# Sheet1.net
KiCad netlist of a schematic drawn in Altium Designer
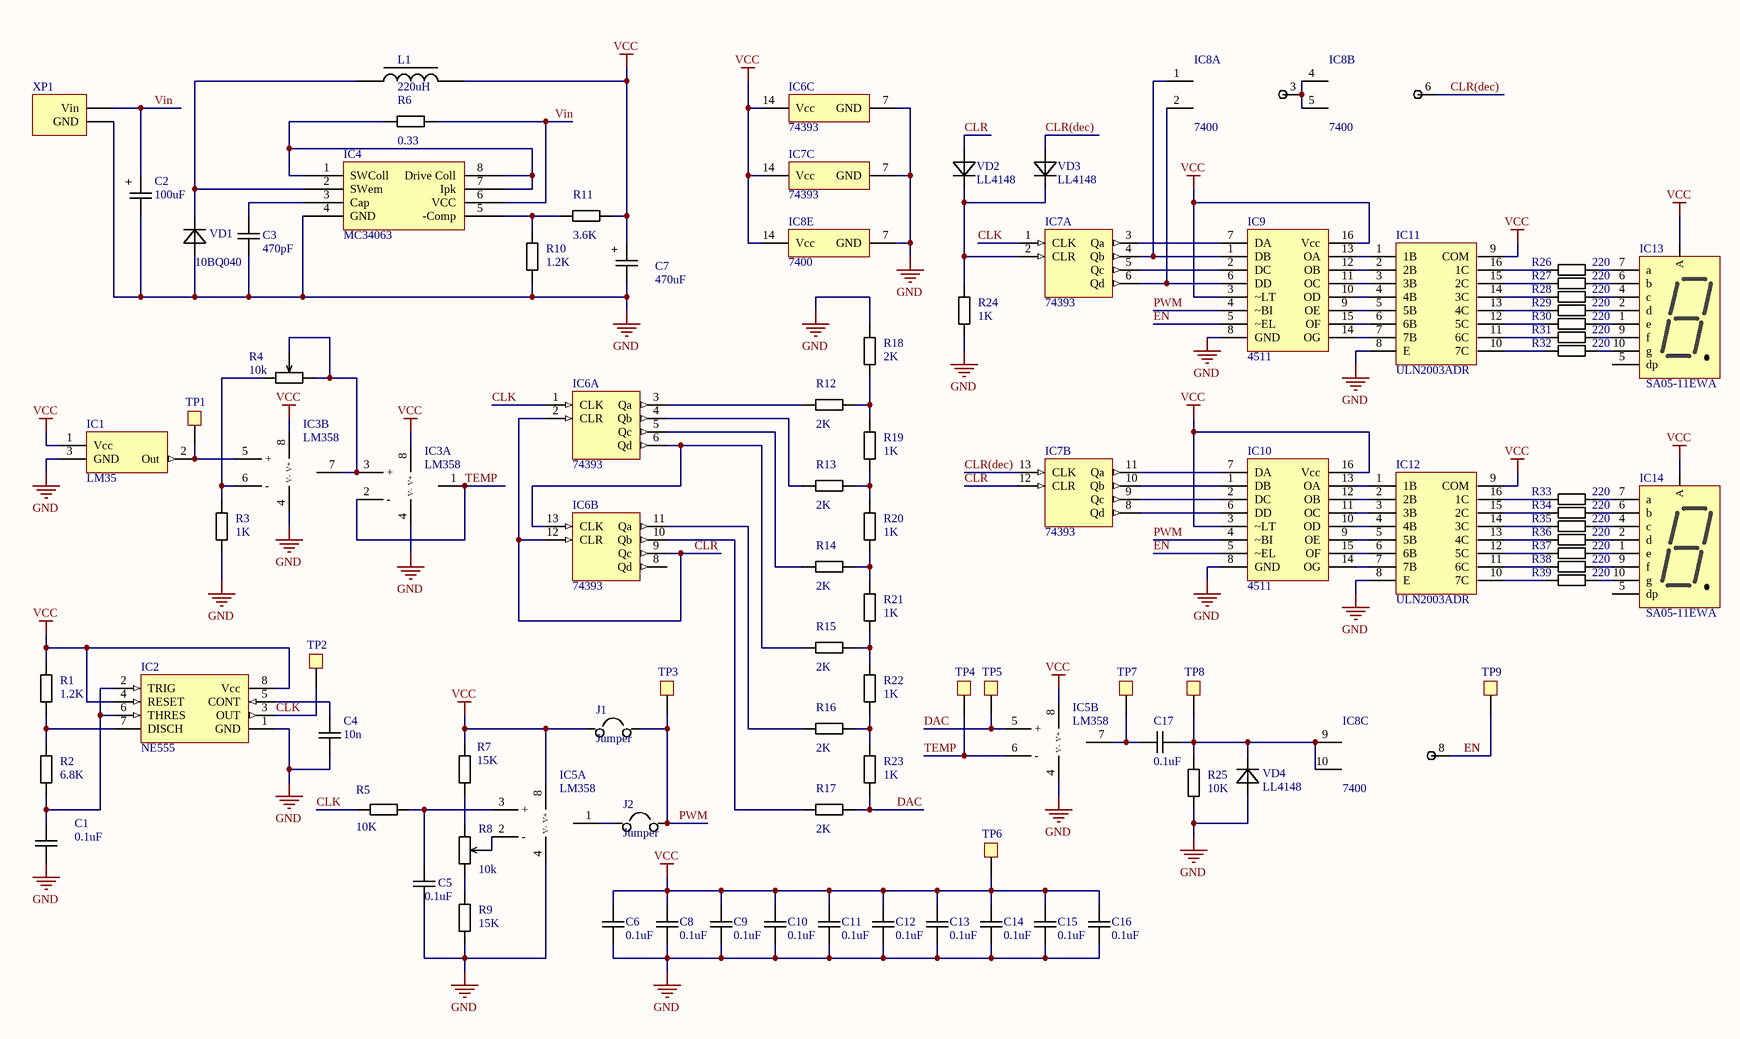
[diagram p0: Sheet1.SchDoc]

(export (version "E")
  (design (tool "Eeschema 10.0.6"))
  (components
    (comp (ref "C1") (value "0.1uF") (footprint "CAP0805") (libsource (lib "Schlib") (part "Cap0805")))
    (comp (ref "C2") (value "100uF") (footprint "CAP-SMD-E") (libsource (lib "Schlib") (part "Cap+")))
    (comp (ref "C3") (value "470pF") (footprint "CAP0805") (libsource (lib "Schlib") (part "Cap0805")))
    (comp (ref "C4") (value "10n") (footprint "CAP0805") (libsource (lib "Schlib") (part "Cap0805")))
    (comp (ref "C5") (value "0.1uF") (footprint "CAP0805") (libsource (lib "Schlib") (part "Cap0805")))
    (comp (ref "C6") (value "0.1uF") (footprint "CAP0805") (libsource (lib "Schlib") (part "Cap0805")))
    (comp (ref "C7") (value "470uF") (footprint "CAP-SMD-E") (libsource (lib "Schlib") (part "Cap+")))
    (comp (ref "C8") (value "0.1uF") (footprint "CAP0805") (libsource (lib "Schlib") (part "Cap0805")))
    (comp (ref "C9") (value "0.1uF") (footprint "CAP0805") (libsource (lib "Schlib") (part "Cap0805")))
    (comp (ref "C10") (value "0.1uF") (footprint "CAP0805") (libsource (lib "Schlib") (part "Cap0805")))
    (comp (ref "C11") (value "0.1uF") (footprint "CAP0805") (libsource (lib "Schlib") (part "Cap0805")))
    (comp (ref "C12") (value "0.1uF") (footprint "CAP0805") (libsource (lib "Schlib") (part "Cap0805")))
    (comp (ref "C13") (value "0.1uF") (footprint "CAP0805") (libsource (lib "Schlib") (part "Cap0805")))
    (comp (ref "C14") (value "0.1uF") (footprint "CAP0805") (libsource (lib "Schlib") (part "Cap0805")))
    (comp (ref "C15") (value "0.1uF") (footprint "CAP0805") (libsource (lib "Schlib") (part "Cap0805")))
    (comp (ref "C16") (value "0.1uF") (footprint "CAP0805") (libsource (lib "Schlib") (part "Cap0805")))
    (comp (ref "C17") (value "0.1uF") (footprint "CAP0805") (libsource (lib "Schlib") (part "Cap0805")))
    (comp (ref "IC1") (value "LM35") (footprint "TO92") (libsource (lib "Schlib") (part "LM35")))
    (comp (ref "IC2") (value "NE555") (footprint "SOIC8") (libsource (lib "Schlib") (part "NE555")))
    (comp (ref "IC3") (value "LM358") (footprint "SOIC8") (libsource (lib "Schlib") (part "LM358")))
    (comp (ref "IC4") (value "MC34063") (footprint "SOIC8") (libsource (lib "Schlib") (part "MC34063")))
    (comp (ref "IC5") (value "LM358") (footprint "SOIC8") (libsource (lib "Schlib") (part "LM358")))
    (comp (ref "IC6") (value "74393") (footprint "SOIC-14(3.9mm)") (libsource (lib "Schlib") (part "74393")))
    (comp (ref "IC7") (value "74393") (footprint "SOIC-14(3.9mm)") (libsource (lib "Schlib") (part "74393")))
    (comp (ref "IC8") (value "7400") (footprint "SOIC-14(3.9mm)") (libsource (lib "Schlib") (part "7400")))
    (comp (ref "IC9") (value "4511") (footprint "DIP16") (libsource (lib "Schlib") (part "4511")))
    (comp (ref "IC10") (value "4511") (footprint "DIP16") (libsource (lib "Schlib") (part "4511")))
    (comp (ref "IC11")
      (value "ULN2003ADR")
      (footprint "SOIC16")
      (libsource (lib "Schlib") (part "ULN2003ADR"))
    )
    (comp (ref "IC12")
      (value "ULN2003ADR")
      (footprint "SOIC16")
      (libsource (lib "Schlib") (part "ULN2003ADR"))
    )
    (comp (ref "IC13")
      (value "SA05-11EWA")
      (footprint "SA05-11EWA")
      (libsource (lib "Schlib") (part "SA05-11EWA"))
    )
    (comp (ref "IC14")
      (value "SA05-11EWA")
      (footprint "SA05-11EWA")
      (libsource (lib "Schlib") (part "SA05-11EWA"))
    )
    (comp (ref "J1") (value "Jumper") (footprint "RES0805") (libsource (lib "Schlib") (part "Jumper0805")))
    (comp (ref "J2") (value "Jumper") (footprint "RES0805") (libsource (lib "Schlib") (part "Jumper0805")))
    (comp (ref "L1") (value "220uH") (footprint "LQH55") (libsource (lib "Schlib") (part "Coil")))
    (comp (ref "R1") (value "1.2K") (footprint "RES0805") (libsource (lib "") (part "Res0805_1")))
    (comp (ref "R2") (value "6.8K") (footprint "RES0805") (libsource (lib "") (part "Res0805_1")))
    (comp (ref "R3") (value "1K") (footprint "RES0805") (libsource (lib "") (part "Res0805_1")))
    (comp (ref "R4") (value "10k") (footprint "POT") (libsource (lib "") (part "POT_1")))
    (comp (ref "R5") (value "10K") (footprint "RES0805") (libsource (lib "") (part "Res0805_2")))
    (comp (ref "R6") (value "0.33") (footprint "RES0805") (libsource (lib "Schlib") (part "Res0805")))
    (comp (ref "R7") (value "15K") (footprint "RES0805") (libsource (lib "") (part "Res0805_3")))
    (comp (ref "R8") (value "10k") (footprint "POT") (libsource (lib "Schlib") (part "POT")))
    (comp (ref "R9") (value "15K") (footprint "RES0805") (libsource (lib "") (part "Res0805_3")))
    (comp (ref "R10") (value "1.2K") (footprint "RES0805") (libsource (lib "") (part "Res0805_1")))
    (comp (ref "R11") (value "3.6K") (footprint "RES0805") (libsource (lib "") (part "Res0805_2")))
    (comp (ref "R12") (value "2K") (footprint "RES0805") (libsource (lib "Schlib") (part "Res0805")))
    (comp (ref "R13") (value "2K") (footprint "RES0805") (libsource (lib "Schlib") (part "Res0805")))
    (comp (ref "R14") (value "2K") (footprint "RES0805") (libsource (lib "Schlib") (part "Res0805")))
    (comp (ref "R15") (value "2K") (footprint "RES0805") (libsource (lib "Schlib") (part "Res0805")))
    (comp (ref "R16") (value "2K") (footprint "RES0805") (libsource (lib "Schlib") (part "Res0805")))
    (comp (ref "R17") (value "2K") (footprint "RES0805") (libsource (lib "Schlib") (part "Res0805")))
    (comp (ref "R18") (value "2K") (footprint "RES0805") (libsource (lib "") (part "Res0805_1")))
    (comp (ref "R19") (value "1K") (footprint "RES0805") (libsource (lib "") (part "Res0805_1")))
    (comp (ref "R20") (value "1K") (footprint "RES0805") (libsource (lib "") (part "Res0805_1")))
    (comp (ref "R21") (value "1K") (footprint "RES0805") (libsource (lib "") (part "Res0805_1")))
    (comp (ref "R22") (value "1K") (footprint "RES0805") (libsource (lib "") (part "Res0805_1")))
    (comp (ref "R23") (value "1K") (footprint "RES0805") (libsource (lib "") (part "Res0805_1")))
    (comp (ref "R24") (value "1K") (footprint "RES0805") (libsource (lib "") (part "Res0805_1")))
    (comp (ref "R25") (value "10K") (footprint "RES0805") (libsource (lib "") (part "Res0805_1")))
    (comp (ref "R26") (value "220") (footprint "RES0805") (libsource (lib "Schlib") (part "Res0805")))
    (comp (ref "R27") (value "220") (footprint "RES0805") (libsource (lib "Schlib") (part "Res0805")))
    (comp (ref "R28") (value "220") (footprint "RES0805") (libsource (lib "Schlib") (part "Res0805")))
    (comp (ref "R29") (value "220") (footprint "RES0805") (libsource (lib "Schlib") (part "Res0805")))
    (comp (ref "R30") (value "220") (footprint "RES0805") (libsource (lib "Schlib") (part "Res0805")))
    (comp (ref "R31") (value "220") (footprint "RES0805") (libsource (lib "Schlib") (part "Res0805")))
    (comp (ref "R32") (value "220") (footprint "RES0805") (libsource (lib "Schlib") (part "Res0805")))
    (comp (ref "R33") (value "220") (footprint "RES0805") (libsource (lib "Schlib") (part "Res0805")))
    (comp (ref "R34") (value "220") (footprint "RES0805") (libsource (lib "Schlib") (part "Res0805")))
    (comp (ref "R35") (value "220") (footprint "RES0805") (libsource (lib "Schlib") (part "Res0805")))
    (comp (ref "R36") (value "220") (footprint "RES0805") (libsource (lib "Schlib") (part "Res0805")))
    (comp (ref "R37") (value "220") (footprint "RES0805") (libsource (lib "Schlib") (part "Res0805")))
    (comp (ref "R38") (value "220") (footprint "RES0805") (libsource (lib "Schlib") (part "Res0805")))
    (comp (ref "R39") (value "220") (footprint "RES0805") (libsource (lib "Schlib") (part "Res0805")))
    (comp (ref "TP1") (value "TestPoint") (footprint "TP") (libsource (lib "Schlib") (part "TestPoint")))
    (comp (ref "TP2") (value "TestPoint") (footprint "TP") (libsource (lib "Schlib") (part "TestPoint")))
    (comp (ref "TP3") (value "TestPoint") (footprint "TP") (libsource (lib "Schlib") (part "TestPoint")))
    (comp (ref "TP4") (value "TestPoint") (footprint "TP") (libsource (lib "Schlib") (part "TestPoint")))
    (comp (ref "TP5") (value "TestPoint") (footprint "TP") (libsource (lib "Schlib") (part "TestPoint")))
    (comp (ref "TP6") (value "TestPoint") (footprint "TP") (libsource (lib "Schlib") (part "TestPoint")))
    (comp (ref "TP7") (value "TestPoint") (footprint "TP") (libsource (lib "Schlib") (part "TestPoint")))
    (comp (ref "TP8") (value "TestPoint") (footprint "TP") (libsource (lib "Schlib") (part "TestPoint")))
    (comp (ref "TP9") (value "TestPoint") (footprint "TP") (libsource (lib "Schlib") (part "TestPoint")))
    (comp (ref "VD1")
      (value "10BQ040")
      (footprint "DIODESMB")
      (libsource (lib "Schlib") (part "10BQ040(diode)"))
    )
    (comp (ref "VD2")
      (value "LL4148")
      (footprint "DIOMELF")
      (libsource (lib "Schlib") (part "LL4148(diode)"))
    )
    (comp (ref "VD3")
      (value "LL4148")
      (footprint "DIOMELF")
      (libsource (lib "Schlib") (part "LL4148(diode)"))
    )
    (comp (ref "VD4")
      (value "LL4148")
      (footprint "DIOMELF")
      (libsource (lib "Schlib") (part "LL4148(diode)"))
    )
    (comp (ref "XP1") (value "XP") (footprint "XP") (libsource (lib "Schlib") (part "XP")))
  )
  (nets
    (net (code "1") (name "/CLK") (class "Default")
      (node (ref "IC2") (pin "3") (pinfunction "OUT_3") (pintype "output"))
      (node (ref "IC6") (pin "1") (pinfunction "CLK_1") (pintype "input"))
      (node (ref "IC7") (pin "1") (pinfunction "CLK_1") (pintype "input"))
      (node (ref "R5") (pin "2") (pinfunction "2_2") (pintype "passive"))
      (node (ref "TP2") (pin "0") (pinfunction "0_0") (pintype "passive"))
    )
    (net (code "2") (name "/CLR") (class "Default")
      (node (ref "IC6") (pin "12") (pinfunction "CLR_12") (pintype "input"))
      (node (ref "IC6") (pin "2") (pinfunction "CLR_2") (pintype "input"))
      (node (ref "IC6") (pin "9") (pinfunction "Qc_9") (pintype "output"))
      (node (ref "IC7") (pin "12") (pinfunction "CLR_12") (pintype "input"))
      (node (ref "VD2") (pin "A") (pinfunction "A_A") (pintype "passive"))
    )
    (net (code "3") (name "/CLR(dec)") (class "Default")
      (node (ref "IC7") (pin "13") (pinfunction "CLK_13") (pintype "input"))
      (node (ref "IC8") (pin "6") (pinfunction "2Y_6") (pintype "passive"))
      (node (ref "VD3") (pin "A") (pinfunction "A_A") (pintype "passive"))
    )
    (net (code "4") (name "/DAC") (class "Default")
      (node (ref "IC5") (pin "5") (pinfunction "+_5") (pintype "passive"))
      (node (ref "R17") (pin "2") (pinfunction "2_2") (pintype "passive"))
      (node (ref "R23") (pin "1") (pinfunction "1_1") (pintype "passive"))
      (node (ref "TP5") (pin "0") (pinfunction "0_0") (pintype "passive"))
    )
    (net (code "5") (name "/EN") (class "Default")
      (node (ref "IC10") (pin "5") (pinfunction "~EL_5") (pintype "passive"))
      (node (ref "IC8") (pin "8") (pinfunction "3Y_8") (pintype "passive"))
      (node (ref "IC9") (pin "5") (pinfunction "~EL_5") (pintype "passive"))
      (node (ref "TP9") (pin "0") (pinfunction "0_0") (pintype "passive"))
    )
    (net (code "6") (name "/PWM") (class "Default")
      (node (ref "IC10") (pin "4") (pinfunction "~BI_4") (pintype "passive"))
      (node (ref "IC9") (pin "4") (pinfunction "~BI_4") (pintype "passive"))
      (node (ref "J1") (pin "2") (pinfunction "2_2") (pintype "passive"))
      (node (ref "J2") (pin "2") (pinfunction "2_2") (pintype "passive"))
      (node (ref "TP3") (pin "0") (pinfunction "0_0") (pintype "passive"))
    )
    (net (code "7") (name "/TEMP") (class "Default")
      (node (ref "IC3") (pin "1") (pinfunction "Q1_1") (pintype "passive"))
      (node (ref "IC3") (pin "2") (pinfunction "-_2") (pintype "passive"))
      (node (ref "IC5") (pin "6") (pinfunction "-_6") (pintype "passive"))
      (node (ref "TP4") (pin "0") (pinfunction "0_0") (pintype "passive"))
    )
    (net (code "8") (name "/Vin") (class "Default")
      (node (ref "C2") (pin "A") (pinfunction "2_A") (pintype "passive"))
      (node (ref "IC4") (pin "6") (pinfunction "VCC_6") (pintype "power_in"))
      (node (ref "R6") (pin "2") (pinfunction "2_2") (pintype "passive"))
      (node (ref "XP1") (pin "V") (pinfunction "Vin_V") (pintype "power_in"))
    )
    (net (code "9") (name "GND") (class "Default")
      (node (ref "C1") (pin "2") (pinfunction "2_2") (pintype "passive"))
      (node (ref "C10") (pin "1") (pinfunction "1_1") (pintype "passive"))
      (node (ref "C11") (pin "1") (pinfunction "1_1") (pintype "passive"))
      (node (ref "C12") (pin "1") (pinfunction "1_1") (pintype "passive"))
      (node (ref "C13") (pin "1") (pinfunction "1_1") (pintype "passive"))
      (node (ref "C14") (pin "1") (pinfunction "1_1") (pintype "passive"))
      (node (ref "C15") (pin "1") (pinfunction "1_1") (pintype "passive"))
      (node (ref "C16") (pin "1") (pinfunction "1_1") (pintype "passive"))
      (node (ref "C2") (pin "C") (pinfunction "1_C") (pintype "passive"))
      (node (ref "C3") (pin "2") (pinfunction "2_2") (pintype "passive"))
      (node (ref "C4") (pin "1") (pinfunction "1_1") (pintype "passive"))
      (node (ref "C5") (pin "1") (pinfunction "1_1") (pintype "passive"))
      (node (ref "C6") (pin "1") (pinfunction "1_1") (pintype "passive"))
      (node (ref "C7") (pin "C") (pinfunction "1_C") (pintype "passive"))
      (node (ref "C8") (pin "1") (pinfunction "1_1") (pintype "passive"))
      (node (ref "C9") (pin "1") (pinfunction "1_1") (pintype "passive"))
      (node (ref "IC1") (pin "3") (pinfunction "GND_3") (pintype "power_in"))
      (node (ref "IC10") (pin "8") (pinfunction "GND_8") (pintype "passive"))
      (node (ref "IC11") (pin "8") (pinfunction "E_8") (pintype "passive"))
      (node (ref "IC12") (pin "8") (pinfunction "E_8") (pintype "passive"))
      (node (ref "IC2") (pin "1") (pinfunction "GND_1") (pintype "power_in"))
      (node (ref "IC3") (pin "4") (pinfunction "V-_4") (pintype "power_in"))
      (node (ref "IC4") (pin "4") (pinfunction "GND_4") (pintype "power_in"))
      (node (ref "IC5") (pin "4") (pinfunction "V-_4") (pintype "power_in"))
      (node (ref "IC6") (pin "7") (pinfunction "GND_7") (pintype "power_in"))
      (node (ref "IC7") (pin "7") (pinfunction "GND_7") (pintype "power_in"))
      (node (ref "IC8") (pin "7") (pinfunction "GND_7") (pintype "power_in"))
      (node (ref "IC9") (pin "8") (pinfunction "GND_8") (pintype "passive"))
      (node (ref "R10") (pin "1") (pinfunction "1_1") (pintype "passive"))
      (node (ref "R18") (pin "2") (pinfunction "2_2") (pintype "passive"))
      (node (ref "R24") (pin "1") (pinfunction "1_1") (pintype "passive"))
      (node (ref "R25") (pin "1") (pinfunction "1_1") (pintype "passive"))
      (node (ref "R3") (pin "1") (pinfunction "1_1") (pintype "passive"))
      (node (ref "R9") (pin "2") (pinfunction "2_2") (pintype "passive"))
      (node (ref "VD1") (pin "A") (pinfunction "A_A") (pintype "passive"))
      (node (ref "VD4") (pin "A") (pinfunction "A_A") (pintype "passive"))
      (node (ref "XP1") (pin "G") (pinfunction "GND_G") (pintype "power_in"))
    )
    (net (code "10") (name "Net-(IC1-Out)") (class "Default")
      (node (ref "IC1") (pin "2") (pinfunction "Out_2") (pintype "output"))
      (node (ref "IC3") (pin "5") (pinfunction "+_5") (pintype "passive"))
      (node (ref "TP1") (pin "0") (pinfunction "0_0") (pintype "passive"))
    )
    (net (code "11") (name "Net-(IC2-CONT)") (class "Default")
      (node (ref "C4") (pin "2") (pinfunction "2_2") (pintype "passive"))
      (node (ref "IC2") (pin "5") (pinfunction "CONT_5") (pintype "input"))
    )
    (net (code "12") (name "Net-(IC2-DISCH)") (class "Default")
      (node (ref "IC2") (pin "7") (pinfunction "DISCH_7") (pintype "passive"))
      (node (ref "R1") (pin "1") (pinfunction "1_1") (pintype "passive"))
      (node (ref "R2") (pin "2") (pinfunction "2_2") (pintype "passive"))
    )
    (net (code "13") (name "Net-(IC2-THRES)") (class "Default")
      (node (ref "C1") (pin "1") (pinfunction "1_1") (pintype "passive"))
      (node (ref "IC2") (pin "2") (pinfunction "TRIG_2") (pintype "input"))
      (node (ref "IC2") (pin "6") (pinfunction "THRES_6") (pintype "input"))
      (node (ref "R2") (pin "1") (pinfunction "1_1") (pintype "passive"))
    )
    (net (code "14") (name "Net-(IC3A-+)") (class "Default")
      (node (ref "IC3") (pin "3") (pinfunction "+_3") (pintype "passive"))
      (node (ref "IC3") (pin "7") (pinfunction "Q2_7") (pintype "passive"))
      (node (ref "R4") (pin "2") (pinfunction "2_2") (pintype "passive"))
      (node (ref "R4") (pin "3") (pinfunction "3_3") (pintype "passive"))
    )
    (net (code "15") (name "Net-(IC3B--)") (class "Default")
      (node (ref "IC3") (pin "6") (pinfunction "-_6") (pintype "passive"))
      (node (ref "R3") (pin "2") (pinfunction "2_2") (pintype "passive"))
      (node (ref "R4") (pin "1") (pinfunction "1_1") (pintype "passive"))
    )
    (net (code "16") (name "Net-(IC4--Comp)") (class "Default")
      (node (ref "IC4") (pin "5") (pinfunction "-Comp_5") (pintype "passive"))
      (node (ref "R10") (pin "2") (pinfunction "2_2") (pintype "passive"))
      (node (ref "R11") (pin "2") (pinfunction "2_2") (pintype "passive"))
    )
    (net (code "17") (name "Net-(IC4-Cap)") (class "Default")
      (node (ref "C3") (pin "1") (pinfunction "1_1") (pintype "passive"))
      (node (ref "IC4") (pin "3") (pinfunction "Cap_3") (pintype "passive"))
    )
    (net (code "18") (name "Net-(IC4-Drive_Coll)") (class "Default")
      (node (ref "IC4") (pin "1") (pinfunction "SWColl_1") (pintype "passive"))
      (node (ref "IC4") (pin "7") (pinfunction "Ipk_7") (pintype "passive"))
      (node (ref "IC4") (pin "8") (pinfunction "Drive_Coll_8") (pintype "passive"))
      (node (ref "R6") (pin "1") (pinfunction "1_1") (pintype "passive"))
    )
    (net (code "19") (name "Net-(IC4-SWem)") (class "Default")
      (node (ref "IC4") (pin "2") (pinfunction "SWem_2") (pintype "passive"))
      (node (ref "L1") (pin "1") (pinfunction "1_1") (pintype "passive"))
      (node (ref "VD1") (pin "C") (pinfunction "C_C") (pintype "passive"))
    )
    (net (code "20") (name "Net-(IC5A-+)") (class "Default")
      (node (ref "C5") (pin "2") (pinfunction "2_2") (pintype "passive"))
      (node (ref "IC5") (pin "3") (pinfunction "+_3") (pintype "passive"))
      (node (ref "R5") (pin "1") (pinfunction "1_1") (pintype "passive"))
    )
    (net (code "21") (name "Net-(IC5A--)") (class "Default")
      (node (ref "IC5") (pin "2") (pinfunction "-_2") (pintype "passive"))
      (node (ref "R8") (pin "3") (pinfunction "3_3") (pintype "passive"))
    )
    (net (code "22") (name "Net-(IC5A-Q1)") (class "Default")
      (node (ref "IC5") (pin "1") (pinfunction "Q1_1") (pintype "passive"))
      (node (ref "J2") (pin "1") (pinfunction "1_1") (pintype "passive"))
    )
    (net (code "23") (name "Net-(IC5B-Q2)") (class "Default")
      (node (ref "C17") (pin "1") (pinfunction "1_1") (pintype "passive"))
      (node (ref "IC5") (pin "7") (pinfunction "Q2_7") (pintype "passive"))
      (node (ref "TP7") (pin "0") (pinfunction "0_0") (pintype "passive"))
    )
    (net (code "24") (name "Net-(IC6A-Qa)") (class "Default")
      (node (ref "IC6") (pin "3") (pinfunction "Qa_3") (pintype "output"))
      (node (ref "R12") (pin "1") (pinfunction "1_1") (pintype "passive"))
    )
    (net (code "25") (name "Net-(IC6A-Qb)") (class "Default")
      (node (ref "IC6") (pin "4") (pinfunction "Qb_4") (pintype "output"))
      (node (ref "R13") (pin "1") (pinfunction "1_1") (pintype "passive"))
    )
    (net (code "26") (name "Net-(IC6A-Qc)") (class "Default")
      (node (ref "IC6") (pin "5") (pinfunction "Qc_5") (pintype "output"))
      (node (ref "R14") (pin "1") (pinfunction "1_1") (pintype "passive"))
    )
    (net (code "27") (name "Net-(IC6A-Qd)") (class "Default")
      (node (ref "IC6") (pin "13") (pinfunction "CLK_13") (pintype "input"))
      (node (ref "IC6") (pin "6") (pinfunction "Qd_6") (pintype "output"))
      (node (ref "R15") (pin "1") (pinfunction "1_1") (pintype "passive"))
    )
    (net (code "28") (name "Net-(IC6B-Qa)") (class "Default")
      (node (ref "IC6") (pin "11") (pinfunction "Qa_11") (pintype "output"))
      (node (ref "R16") (pin "1") (pinfunction "1_1") (pintype "passive"))
    )
    (net (code "29") (name "Net-(IC6B-Qb)") (class "Default")
      (node (ref "IC6") (pin "10") (pinfunction "Qb_10") (pintype "output"))
      (node (ref "R17") (pin "1") (pinfunction "1_1") (pintype "passive"))
    )
    (net (code "30") (name "Net-(IC7A-CLR)") (class "Default")
      (node (ref "IC7") (pin "2") (pinfunction "CLR_2") (pintype "input"))
      (node (ref "R24") (pin "2") (pinfunction "2_2") (pintype "passive"))
      (node (ref "VD2") (pin "C") (pinfunction "C_C") (pintype "passive"))
      (node (ref "VD3") (pin "C") (pinfunction "C_C") (pintype "passive"))
    )
    (net (code "31") (name "Net-(IC7A-Qa)") (class "Default")
      (node (ref "IC7") (pin "3") (pinfunction "Qa_3") (pintype "output"))
      (node (ref "IC9") (pin "7") (pinfunction "DA_7") (pintype "passive"))
    )
    (net (code "32") (name "Net-(IC7A-Qb)") (class "Default")
      (node (ref "IC7") (pin "4") (pinfunction "Qb_4") (pintype "output"))
      (node (ref "IC8") (pin "1") (pinfunction "1A_1") (pintype "passive"))
      (node (ref "IC9") (pin "1") (pinfunction "DB_1") (pintype "passive"))
    )
    (net (code "33") (name "Net-(IC7A-Qc)") (class "Default")
      (node (ref "IC7") (pin "5") (pinfunction "Qc_5") (pintype "output"))
      (node (ref "IC9") (pin "2") (pinfunction "DC_2") (pintype "passive"))
    )
    (net (code "34") (name "Net-(IC7A-Qd)") (class "Default")
      (node (ref "IC7") (pin "6") (pinfunction "Qd_6") (pintype "output"))
      (node (ref "IC8") (pin "2") (pinfunction "1B_2") (pintype "passive"))
      (node (ref "IC9") (pin "6") (pinfunction "DD_6") (pintype "passive"))
    )
    (net (code "35") (name "Net-(IC8A-1Y)") (class "Default")
      (node (ref "IC8") (pin "3") (pinfunction "1Y_3") (pintype "passive"))
      (node (ref "IC8") (pin "4") (pinfunction "2A_4") (pintype "passive"))
      (node (ref "IC8") (pin "5") (pinfunction "2B_5") (pintype "passive"))
    )
    (net (code "36") (name "Net-(IC8C-3A)") (class "Default")
      (node (ref "C17") (pin "2") (pinfunction "2_2") (pintype "passive"))
      (node (ref "IC8") (pin "10") (pinfunction "3B_10") (pintype "passive"))
      (node (ref "IC8") (pin "9") (pinfunction "3A_9") (pintype "passive"))
      (node (ref "R25") (pin "2") (pinfunction "2_2") (pintype "passive"))
      (node (ref "TP8") (pin "0") (pinfunction "0_0") (pintype "passive"))
      (node (ref "VD4") (pin "C") (pinfunction "C_C") (pintype "passive"))
    )
    (net (code "37") (name "Net-(IC10-DA)") (class "Default")
      (node (ref "IC10") (pin "7") (pinfunction "DA_7") (pintype "passive"))
      (node (ref "IC7") (pin "11") (pinfunction "Qa_11") (pintype "output"))
    )
    (net (code "38") (name "Net-(IC10-DB)") (class "Default")
      (node (ref "IC10") (pin "1") (pinfunction "DB_1") (pintype "passive"))
      (node (ref "IC7") (pin "10") (pinfunction "Qb_10") (pintype "output"))
    )
    (net (code "39") (name "Net-(IC10-DC)") (class "Default")
      (node (ref "IC10") (pin "2") (pinfunction "DC_2") (pintype "passive"))
      (node (ref "IC7") (pin "9") (pinfunction "Qc_9") (pintype "output"))
    )
    (net (code "40") (name "Net-(IC10-DD)") (class "Default")
      (node (ref "IC10") (pin "6") (pinfunction "DD_6") (pintype "passive"))
      (node (ref "IC7") (pin "8") (pinfunction "Qd_8") (pintype "output"))
    )
    (net (code "41") (name "Net-(IC10-OA)") (class "Default")
      (node (ref "IC10") (pin "13") (pinfunction "OA_13") (pintype "passive"))
      (node (ref "IC12") (pin "1") (pinfunction "1B_1") (pintype "passive"))
    )
    (net (code "42") (name "Net-(IC10-OB)") (class "Default")
      (node (ref "IC10") (pin "12") (pinfunction "OB_12") (pintype "passive"))
      (node (ref "IC12") (pin "2") (pinfunction "2B_2") (pintype "passive"))
    )
    (net (code "43") (name "Net-(IC10-OC)") (class "Default")
      (node (ref "IC10") (pin "11") (pinfunction "OC_11") (pintype "passive"))
      (node (ref "IC12") (pin "3") (pinfunction "3B_3") (pintype "passive"))
    )
    (net (code "44") (name "Net-(IC10-OD)") (class "Default")
      (node (ref "IC10") (pin "10") (pinfunction "OD_10") (pintype "passive"))
      (node (ref "IC12") (pin "4") (pinfunction "4B_4") (pintype "passive"))
    )
    (net (code "45") (name "Net-(IC10-OE)") (class "Default")
      (node (ref "IC10") (pin "9") (pinfunction "OE_9") (pintype "passive"))
      (node (ref "IC12") (pin "5") (pinfunction "5B_5") (pintype "passive"))
    )
    (net (code "46") (name "Net-(IC10-OF)") (class "Default")
      (node (ref "IC10") (pin "15") (pinfunction "OF_15") (pintype "passive"))
      (node (ref "IC12") (pin "6") (pinfunction "6B_6") (pintype "passive"))
    )
    (net (code "47") (name "Net-(IC10-OG)") (class "Default")
      (node (ref "IC10") (pin "14") (pinfunction "OG_14") (pintype "passive"))
      (node (ref "IC12") (pin "7") (pinfunction "7B_7") (pintype "passive"))
    )
    (net (code "48") (name "Net-(IC11-1B)") (class "Default")
      (node (ref "IC11") (pin "1") (pinfunction "1B_1") (pintype "passive"))
      (node (ref "IC9") (pin "13") (pinfunction "OA_13") (pintype "passive"))
    )
    (net (code "49") (name "Net-(IC11-1C)") (class "Default")
      (node (ref "IC11") (pin "16") (pinfunction "1C_16") (pintype "passive"))
      (node (ref "R26") (pin "1") (pinfunction "1_1") (pintype "passive"))
    )
    (net (code "50") (name "Net-(IC11-2B)") (class "Default")
      (node (ref "IC11") (pin "2") (pinfunction "2B_2") (pintype "passive"))
      (node (ref "IC9") (pin "12") (pinfunction "OB_12") (pintype "passive"))
    )
    (net (code "51") (name "Net-(IC11-2C)") (class "Default")
      (node (ref "IC11") (pin "15") (pinfunction "2C_15") (pintype "passive"))
      (node (ref "R27") (pin "1") (pinfunction "1_1") (pintype "passive"))
    )
    (net (code "52") (name "Net-(IC11-3B)") (class "Default")
      (node (ref "IC11") (pin "3") (pinfunction "3B_3") (pintype "passive"))
      (node (ref "IC9") (pin "11") (pinfunction "OC_11") (pintype "passive"))
    )
    (net (code "53") (name "Net-(IC11-3C)") (class "Default")
      (node (ref "IC11") (pin "14") (pinfunction "3C_14") (pintype "passive"))
      (node (ref "R28") (pin "1") (pinfunction "1_1") (pintype "passive"))
    )
    (net (code "54") (name "Net-(IC11-4B)") (class "Default")
      (node (ref "IC11") (pin "4") (pinfunction "4B_4") (pintype "passive"))
      (node (ref "IC9") (pin "10") (pinfunction "OD_10") (pintype "passive"))
    )
    (net (code "55") (name "Net-(IC11-4C)") (class "Default")
      (node (ref "IC11") (pin "13") (pinfunction "4C_13") (pintype "passive"))
      (node (ref "R29") (pin "1") (pinfunction "1_1") (pintype "passive"))
    )
    (net (code "56") (name "Net-(IC11-5B)") (class "Default")
      (node (ref "IC11") (pin "5") (pinfunction "5B_5") (pintype "passive"))
      (node (ref "IC9") (pin "9") (pinfunction "OE_9") (pintype "passive"))
    )
    (net (code "57") (name "Net-(IC11-5C)") (class "Default")
      (node (ref "IC11") (pin "12") (pinfunction "5C_12") (pintype "passive"))
      (node (ref "R30") (pin "1") (pinfunction "1_1") (pintype "passive"))
    )
    (net (code "58") (name "Net-(IC11-6B)") (class "Default")
      (node (ref "IC11") (pin "6") (pinfunction "6B_6") (pintype "passive"))
      (node (ref "IC9") (pin "15") (pinfunction "OF_15") (pintype "passive"))
    )
    (net (code "59") (name "Net-(IC11-6C)") (class "Default")
      (node (ref "IC11") (pin "11") (pinfunction "6C_11") (pintype "passive"))
      (node (ref "R31") (pin "1") (pinfunction "1_1") (pintype "passive"))
    )
    (net (code "60") (name "Net-(IC11-7B)") (class "Default")
      (node (ref "IC11") (pin "7") (pinfunction "7B_7") (pintype "passive"))
      (node (ref "IC9") (pin "14") (pinfunction "OG_14") (pintype "passive"))
    )
    (net (code "61") (name "Net-(IC11-7C)") (class "Default")
      (node (ref "IC11") (pin "10") (pinfunction "7C_10") (pintype "passive"))
      (node (ref "R32") (pin "1") (pinfunction "1_1") (pintype "passive"))
    )
    (net (code "62") (name "Net-(IC12-1C)") (class "Default")
      (node (ref "IC12") (pin "16") (pinfunction "1C_16") (pintype "passive"))
      (node (ref "R33") (pin "1") (pinfunction "1_1") (pintype "passive"))
    )
    (net (code "63") (name "Net-(IC12-2C)") (class "Default")
      (node (ref "IC12") (pin "15") (pinfunction "2C_15") (pintype "passive"))
      (node (ref "R34") (pin "1") (pinfunction "1_1") (pintype "passive"))
    )
    (net (code "64") (name "Net-(IC12-3C)") (class "Default")
      (node (ref "IC12") (pin "14") (pinfunction "3C_14") (pintype "passive"))
      (node (ref "R35") (pin "1") (pinfunction "1_1") (pintype "passive"))
    )
    (net (code "65") (name "Net-(IC12-4C)") (class "Default")
      (node (ref "IC12") (pin "13") (pinfunction "4C_13") (pintype "passive"))
      (node (ref "R36") (pin "1") (pinfunction "1_1") (pintype "passive"))
    )
    (net (code "66") (name "Net-(IC12-5C)") (class "Default")
      (node (ref "IC12") (pin "12") (pinfunction "5C_12") (pintype "passive"))
      (node (ref "R37") (pin "1") (pinfunction "1_1") (pintype "passive"))
    )
    (net (code "67") (name "Net-(IC12-6C)") (class "Default")
      (node (ref "IC12") (pin "11") (pinfunction "6C_11") (pintype "passive"))
      (node (ref "R38") (pin "1") (pinfunction "1_1") (pintype "passive"))
    )
    (net (code "68") (name "Net-(IC12-7C)") (class "Default")
      (node (ref "IC12") (pin "10") (pinfunction "7C_10") (pintype "passive"))
      (node (ref "R39") (pin "1") (pinfunction "1_1") (pintype "passive"))
    )
    (net (code "69") (name "Net-(IC13-a)") (class "Default")
      (node (ref "IC13") (pin "7") (pinfunction "a_7") (pintype "power_in"))
      (node (ref "R26") (pin "2") (pinfunction "2_2") (pintype "passive"))
    )
    (net (code "70") (name "Net-(IC13-b)") (class "Default")
      (node (ref "IC13") (pin "6") (pinfunction "b_6") (pintype "power_in"))
      (node (ref "R27") (pin "2") (pinfunction "2_2") (pintype "passive"))
    )
    (net (code "71") (name "Net-(IC13-c)") (class "Default")
      (node (ref "IC13") (pin "4") (pinfunction "c_4") (pintype "power_in"))
      (node (ref "R28") (pin "2") (pinfunction "2_2") (pintype "passive"))
    )
    (net (code "72") (name "Net-(IC13-d)") (class "Default")
      (node (ref "IC13") (pin "2") (pinfunction "d_2") (pintype "power_in"))
      (node (ref "R29") (pin "2") (pinfunction "2_2") (pintype "passive"))
    )
    (net (code "73") (name "Net-(IC13-e)") (class "Default")
      (node (ref "IC13") (pin "1") (pinfunction "e_1") (pintype "power_in"))
      (node (ref "R30") (pin "2") (pinfunction "2_2") (pintype "passive"))
    )
    (net (code "74") (name "Net-(IC13-f)") (class "Default")
      (node (ref "IC13") (pin "9") (pinfunction "f_9") (pintype "power_in"))
      (node (ref "R31") (pin "2") (pinfunction "2_2") (pintype "passive"))
    )
    (net (code "75") (name "Net-(IC13-g)") (class "Default")
      (node (ref "IC13") (pin "10") (pinfunction "g_10") (pintype "power_in"))
      (node (ref "R32") (pin "2") (pinfunction "2_2") (pintype "passive"))
    )
    (net (code "76") (name "Net-(IC14-a)") (class "Default")
      (node (ref "IC14") (pin "7") (pinfunction "a_7") (pintype "power_in"))
      (node (ref "R33") (pin "2") (pinfunction "2_2") (pintype "passive"))
    )
    (net (code "77") (name "Net-(IC14-b)") (class "Default")
      (node (ref "IC14") (pin "6") (pinfunction "b_6") (pintype "power_in"))
      (node (ref "R34") (pin "2") (pinfunction "2_2") (pintype "passive"))
    )
    (net (code "78") (name "Net-(IC14-c)") (class "Default")
      (node (ref "IC14") (pin "4") (pinfunction "c_4") (pintype "power_in"))
      (node (ref "R35") (pin "2") (pinfunction "2_2") (pintype "passive"))
    )
    (net (code "79") (name "Net-(IC14-d)") (class "Default")
      (node (ref "IC14") (pin "2") (pinfunction "d_2") (pintype "power_in"))
      (node (ref "R36") (pin "2") (pinfunction "2_2") (pintype "passive"))
    )
    (net (code "80") (name "Net-(IC14-e)") (class "Default")
      (node (ref "IC14") (pin "1") (pinfunction "e_1") (pintype "power_in"))
      (node (ref "R37") (pin "2") (pinfunction "2_2") (pintype "passive"))
    )
    (net (code "81") (name "Net-(IC14-f)") (class "Default")
      (node (ref "IC14") (pin "9") (pinfunction "f_9") (pintype "power_in"))
      (node (ref "R38") (pin "2") (pinfunction "2_2") (pintype "passive"))
    )
    (net (code "82") (name "Net-(IC14-g)") (class "Default")
      (node (ref "IC14") (pin "10") (pinfunction "g_10") (pintype "power_in"))
      (node (ref "R39") (pin "2") (pinfunction "2_2") (pintype "passive"))
    )
    (net (code "83") (name "Net-(R7-Pad2)") (class "Default")
      (node (ref "R7") (pin "2") (pinfunction "2_2") (pintype "passive"))
      (node (ref "R8") (pin "1") (pinfunction "1_1") (pintype "passive"))
    )
    (net (code "84") (name "Net-(R8-Pad2)") (class "Default")
      (node (ref "R8") (pin "2") (pinfunction "2_2") (pintype "passive"))
      (node (ref "R9") (pin "1") (pinfunction "1_1") (pintype "passive"))
    )
    (net (code "85") (name "Net-(R12-Pad2)") (class "Default")
      (node (ref "R12") (pin "2") (pinfunction "2_2") (pintype "passive"))
      (node (ref "R18") (pin "1") (pinfunction "1_1") (pintype "passive"))
      (node (ref "R19") (pin "2") (pinfunction "2_2") (pintype "passive"))
    )
    (net (code "86") (name "Net-(R13-Pad2)") (class "Default")
      (node (ref "R13") (pin "2") (pinfunction "2_2") (pintype "passive"))
      (node (ref "R19") (pin "1") (pinfunction "1_1") (pintype "passive"))
      (node (ref "R20") (pin "2") (pinfunction "2_2") (pintype "passive"))
    )
    (net (code "87") (name "Net-(R14-Pad2)") (class "Default")
      (node (ref "R14") (pin "2") (pinfunction "2_2") (pintype "passive"))
      (node (ref "R20") (pin "1") (pinfunction "1_1") (pintype "passive"))
      (node (ref "R21") (pin "2") (pinfunction "2_2") (pintype "passive"))
    )
    (net (code "88") (name "Net-(R15-Pad2)") (class "Default")
      (node (ref "R15") (pin "2") (pinfunction "2_2") (pintype "passive"))
      (node (ref "R21") (pin "1") (pinfunction "1_1") (pintype "passive"))
      (node (ref "R22") (pin "2") (pinfunction "2_2") (pintype "passive"))
    )
    (net (code "89") (name "Net-(R16-Pad2)") (class "Default")
      (node (ref "R16") (pin "2") (pinfunction "2_2") (pintype "passive"))
      (node (ref "R22") (pin "1") (pinfunction "1_1") (pintype "passive"))
      (node (ref "R23") (pin "2") (pinfunction "2_2") (pintype "passive"))
    )
    (net (code "90") (name "VCC") (class "Default")
      (node (ref "C10") (pin "2") (pinfunction "2_2") (pintype "passive"))
      (node (ref "C11") (pin "2") (pinfunction "2_2") (pintype "passive"))
      (node (ref "C12") (pin "2") (pinfunction "2_2") (pintype "passive"))
      (node (ref "C13") (pin "2") (pinfunction "2_2") (pintype "passive"))
      (node (ref "C14") (pin "2") (pinfunction "2_2") (pintype "passive"))
      (node (ref "C15") (pin "2") (pinfunction "2_2") (pintype "passive"))
      (node (ref "C16") (pin "2") (pinfunction "2_2") (pintype "passive"))
      (node (ref "C6") (pin "2") (pinfunction "2_2") (pintype "passive"))
      (node (ref "C7") (pin "A") (pinfunction "2_A") (pintype "passive"))
      (node (ref "C8") (pin "2") (pinfunction "2_2") (pintype "passive"))
      (node (ref "C9") (pin "2") (pinfunction "2_2") (pintype "passive"))
      (node (ref "IC1") (pin "1") (pinfunction "Vcc_1") (pintype "power_in"))
      (node (ref "IC10") (pin "16") (pinfunction "Vcc_16") (pintype "passive"))
      (node (ref "IC10") (pin "3") (pinfunction "~LT_3") (pintype "passive"))
      (node (ref "IC11") (pin "9") (pinfunction "COM_9") (pintype "passive"))
      (node (ref "IC12") (pin "9") (pinfunction "COM_9") (pintype "passive"))
      (node (ref "IC13") (pin "A") (pinfunction "A_A") (pintype "power_in"))
      (node (ref "IC14") (pin "A") (pinfunction "A_A") (pintype "power_in"))
      (node (ref "IC2") (pin "4") (pinfunction "RESET_4") (pintype "input"))
      (node (ref "IC2") (pin "8") (pinfunction "Vcc_8") (pintype "power_in"))
      (node (ref "IC3") (pin "8") (pinfunction "V+_8") (pintype "power_in"))
      (node (ref "IC5") (pin "8") (pinfunction "V+_8") (pintype "power_in"))
      (node (ref "IC6") (pin "14") (pinfunction "Vcc_14") (pintype "power_in"))
      (node (ref "IC7") (pin "14") (pinfunction "Vcc_14") (pintype "power_in"))
      (node (ref "IC8") (pin "14") (pinfunction "Vcc_14") (pintype "power_in"))
      (node (ref "IC9") (pin "16") (pinfunction "Vcc_16") (pintype "passive"))
      (node (ref "IC9") (pin "3") (pinfunction "~LT_3") (pintype "passive"))
      (node (ref "J1") (pin "1") (pinfunction "1_1") (pintype "passive"))
      (node (ref "L1") (pin "2") (pinfunction "2_2") (pintype "passive"))
      (node (ref "R1") (pin "2") (pinfunction "2_2") (pintype "passive"))
      (node (ref "R11") (pin "1") (pinfunction "1_1") (pintype "passive"))
      (node (ref "R7") (pin "1") (pinfunction "1_1") (pintype "passive"))
      (node (ref "TP6") (pin "0") (pinfunction "0_0") (pintype "passive"))
    )
    (net (code "91") (name "unconnected-(IC6B-Qd-Pad8)") (class "Default")
      (node (ref "IC6") (pin "8") (pinfunction "Qd_8") (pintype "output"))
    )
    (net (code "92") (name "unconnected-(IC13-dp-Pad5)") (class "Default")
      (node (ref "IC13") (pin "5") (pinfunction "dp_5") (pintype "power_in"))
    )
    (net (code "93") (name "unconnected-(IC14-dp-Pad5)") (class "Default")
      (node (ref "IC14") (pin "5") (pinfunction "dp_5") (pintype "power_in"))
    )
  )
)
